# Servo_Word_Clock_LED_board_u_v1.net
KiCad netlist of a schematic drawn in EAGLE
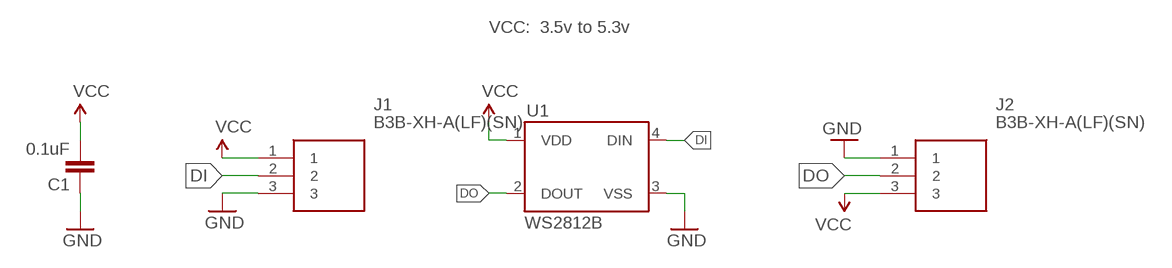
[diagram p0: schematic, sheet 1]

(export (version "E")
  (design (tool "Eeschema 10.0.6"))
  (components
    (comp (ref "C1")
      (value "0.1uF")
      (footprint "eagle-import:0603-CAP")
      (libsource (lib "eagle-import") (part "0.1UF-25V(+80/-20%)(0603)"))
    )
    (comp (ref "J1")
      (value "B3B-XH-A(LF)(SN)")
      (footprint "eagle-import:SHDR3W64P0X250_1X3_990X575X700")
      (fields (field (name "RS_PART_NUMBER") "8201557P"))
      (libsource (lib "eagle-import") (part "B3B-XH-A(LF)(SN)"))
    )
    (comp (ref "J2")
      (value "B3B-XH-A(LF)(SN)")
      (footprint "eagle-import:SHDR3W64P0X250_1X3_990X575X700")
      (fields (field (name "RS_PART_NUMBER") "8201557P"))
      (libsource (lib "eagle-import") (part "B3B-XH-A(LF)(SN)"))
    )
    (comp (ref "U1")
      (value "WS2812B")
      (footprint "eagle-import:WS2812B")
      (libsource (lib "eagle-import") (part "WS2812B"))
    )
  )
  (nets
    (net (code "1") (name "DI") (class "Default")
      (node (ref "J1") (pin "2") (pinfunction "2_2") (pintype "bidirectional"))
      (node (ref "U1") (pin "4") (pinfunction "DIN_4") (pintype "input"))
    )
    (net (code "2") (name "DO") (class "Default")
      (node (ref "J2") (pin "2") (pinfunction "2_2") (pintype "bidirectional"))
      (node (ref "U1") (pin "2") (pinfunction "DOUT_2") (pintype "output"))
    )
    (net (code "3") (name "GND") (class "Default")
      (node (ref "C1") (pin "1") (pinfunction "1_1") (pintype "passive"))
      (node (ref "J1") (pin "3") (pinfunction "3_3") (pintype "bidirectional"))
      (node (ref "J2") (pin "1") (pinfunction "1_1") (pintype "bidirectional"))
      (node (ref "U1") (pin "3") (pinfunction "VSS_3") (pintype "power_in"))
    )
    (net (code "4") (name "VCC") (class "Default")
      (node (ref "C1") (pin "2") (pinfunction "2_2") (pintype "passive"))
      (node (ref "J1") (pin "1") (pinfunction "1_1") (pintype "bidirectional"))
      (node (ref "J2") (pin "3") (pinfunction "3_3") (pintype "bidirectional"))
      (node (ref "U1") (pin "1") (pinfunction "VDD_1") (pintype "power_in"))
    )
  )
)
